# LB_w10_INVERTER_v03_rev1.net
KiCad netlist of a schematic drawn in EAGLE
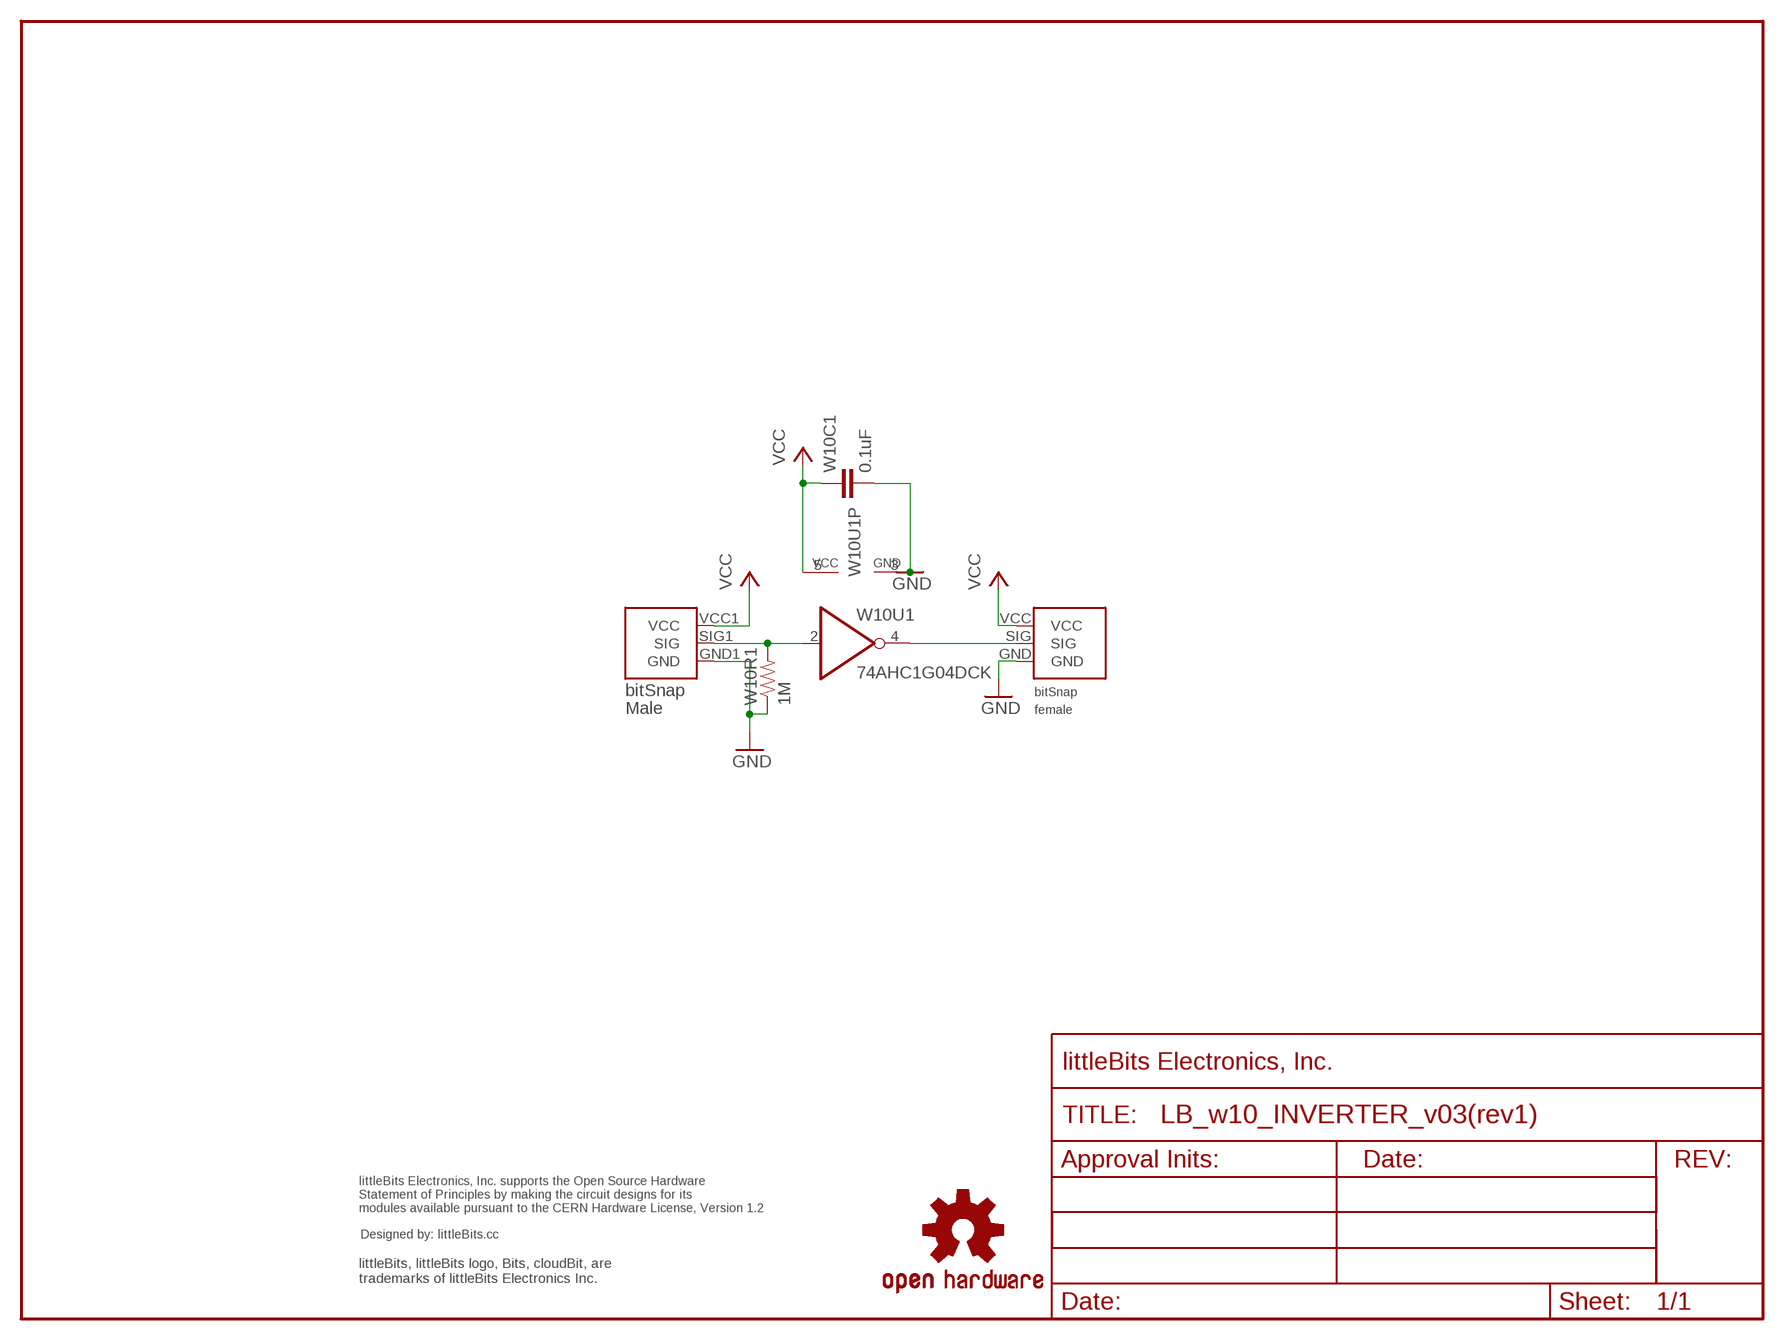
[diagram p0: schematic, sheet 1]

(export (version "E")
  (design (tool "Eeschema 10.0.6"))
  (components
    (comp (ref "U$1")
      (value "FRAME-LETTER-OHWOHW")
      (footprint "eagle-import:FABDWG01-OHW")
      (libsource (lib "eagle-import") (part "FRAME-LETTER-OHWOHW"))
    )
    (comp (ref "U$3")
      (value "OSHWCREDIT")
      (footprint "eagle-import:OSHWCREDIT")
      (libsource (lib "eagle-import") (part "OSHWCREDIT"))
    )
    (comp (ref "U$4")
      (value "OSHW-LOGOL")
      (footprint "eagle-import:OSHW-LOGO-L")
      (libsource (lib "eagle-import") (part "OSHW-LOGOL"))
    )
    (comp (ref "W10BSF1")
      (value "BITSNAP_V03_FEMALE")
      (footprint "eagle-import:BITSNAP_V03_FEMALE")
      (libsource (lib "eagle-import") (part "BITSNAP_V03_FEMALE"))
    )
    (comp (ref "W10BSM1")
      (value "BITSNAP_V03_MALE")
      (footprint "eagle-import:BITSNAP_V03_MALE")
      (libsource (lib "eagle-import") (part "BITSNAP_V03_MALE"))
    )
    (comp (ref "W10C1")
      (value "0.1uF")
      (footprint "eagle-import:0603-CAP")
      (libsource (lib "eagle-import") (part "CAP0603-CAP"))
    )
    (comp (ref "W10R1")
      (value "1M")
      (footprint "eagle-import:0603-RES")
      (libsource (lib "eagle-import") (part "RESISTOR0603-RES"))
    )
    (comp (ref "W10U1")
      (value "74AHC1G04DCK")
      (footprint "eagle-import:SC70-5")
      (libsource (lib "eagle-import") (part "741G04DCKAHC"))
    )
  )
  (nets
    (net (code "1") (name "GND") (class "Default")
      (node (ref "W10BSF1") (pin "GND") (pinfunction "GND_GND") (pintype "bidirectional"))
      (node (ref "W10BSM1") (pin "GND1") (pinfunction "GND_GND1") (pintype "bidirectional"))
      (node (ref "W10C1") (pin "2") (pinfunction "2_2") (pintype "passive"))
      (node (ref "W10R1") (pin "1") (pinfunction "1_1") (pintype "passive"))
      (node (ref "W10U1") (pin "3") (pinfunction "GND_3") (pintype "power_in"))
    )
    (net (code "2") (name "Net-(W10BSM1-SIG)") (class "Default")
      (node (ref "W10BSM1") (pin "SIG1") (pinfunction "SIG_SIG1") (pintype "bidirectional"))
      (node (ref "W10R1") (pin "2") (pinfunction "2_2") (pintype "passive"))
      (node (ref "W10U1") (pin "2") (pinfunction "I_2") (pintype "input"))
    )
    (net (code "3") (name "Net-(W10U1A-O)") (class "Default")
      (node (ref "W10BSF1") (pin "SIG") (pinfunction "SIG_SIG") (pintype "bidirectional"))
      (node (ref "W10U1") (pin "4") (pinfunction "O_4") (pintype "output"))
    )
    (net (code "4") (name "VCC") (class "Default")
      (node (ref "W10BSF1") (pin "VCC") (pinfunction "VCC_VCC") (pintype "bidirectional"))
      (node (ref "W10BSM1") (pin "VCC1") (pinfunction "VCC_VCC1") (pintype "bidirectional"))
      (node (ref "W10C1") (pin "1") (pinfunction "1_1") (pintype "passive"))
      (node (ref "W10U1") (pin "5") (pinfunction "VCC_5") (pintype "power_in"))
    )
  )
)
